# Dart_Controller_SCH.net
KiCad netlist of a schematic drawn in Altium Designer
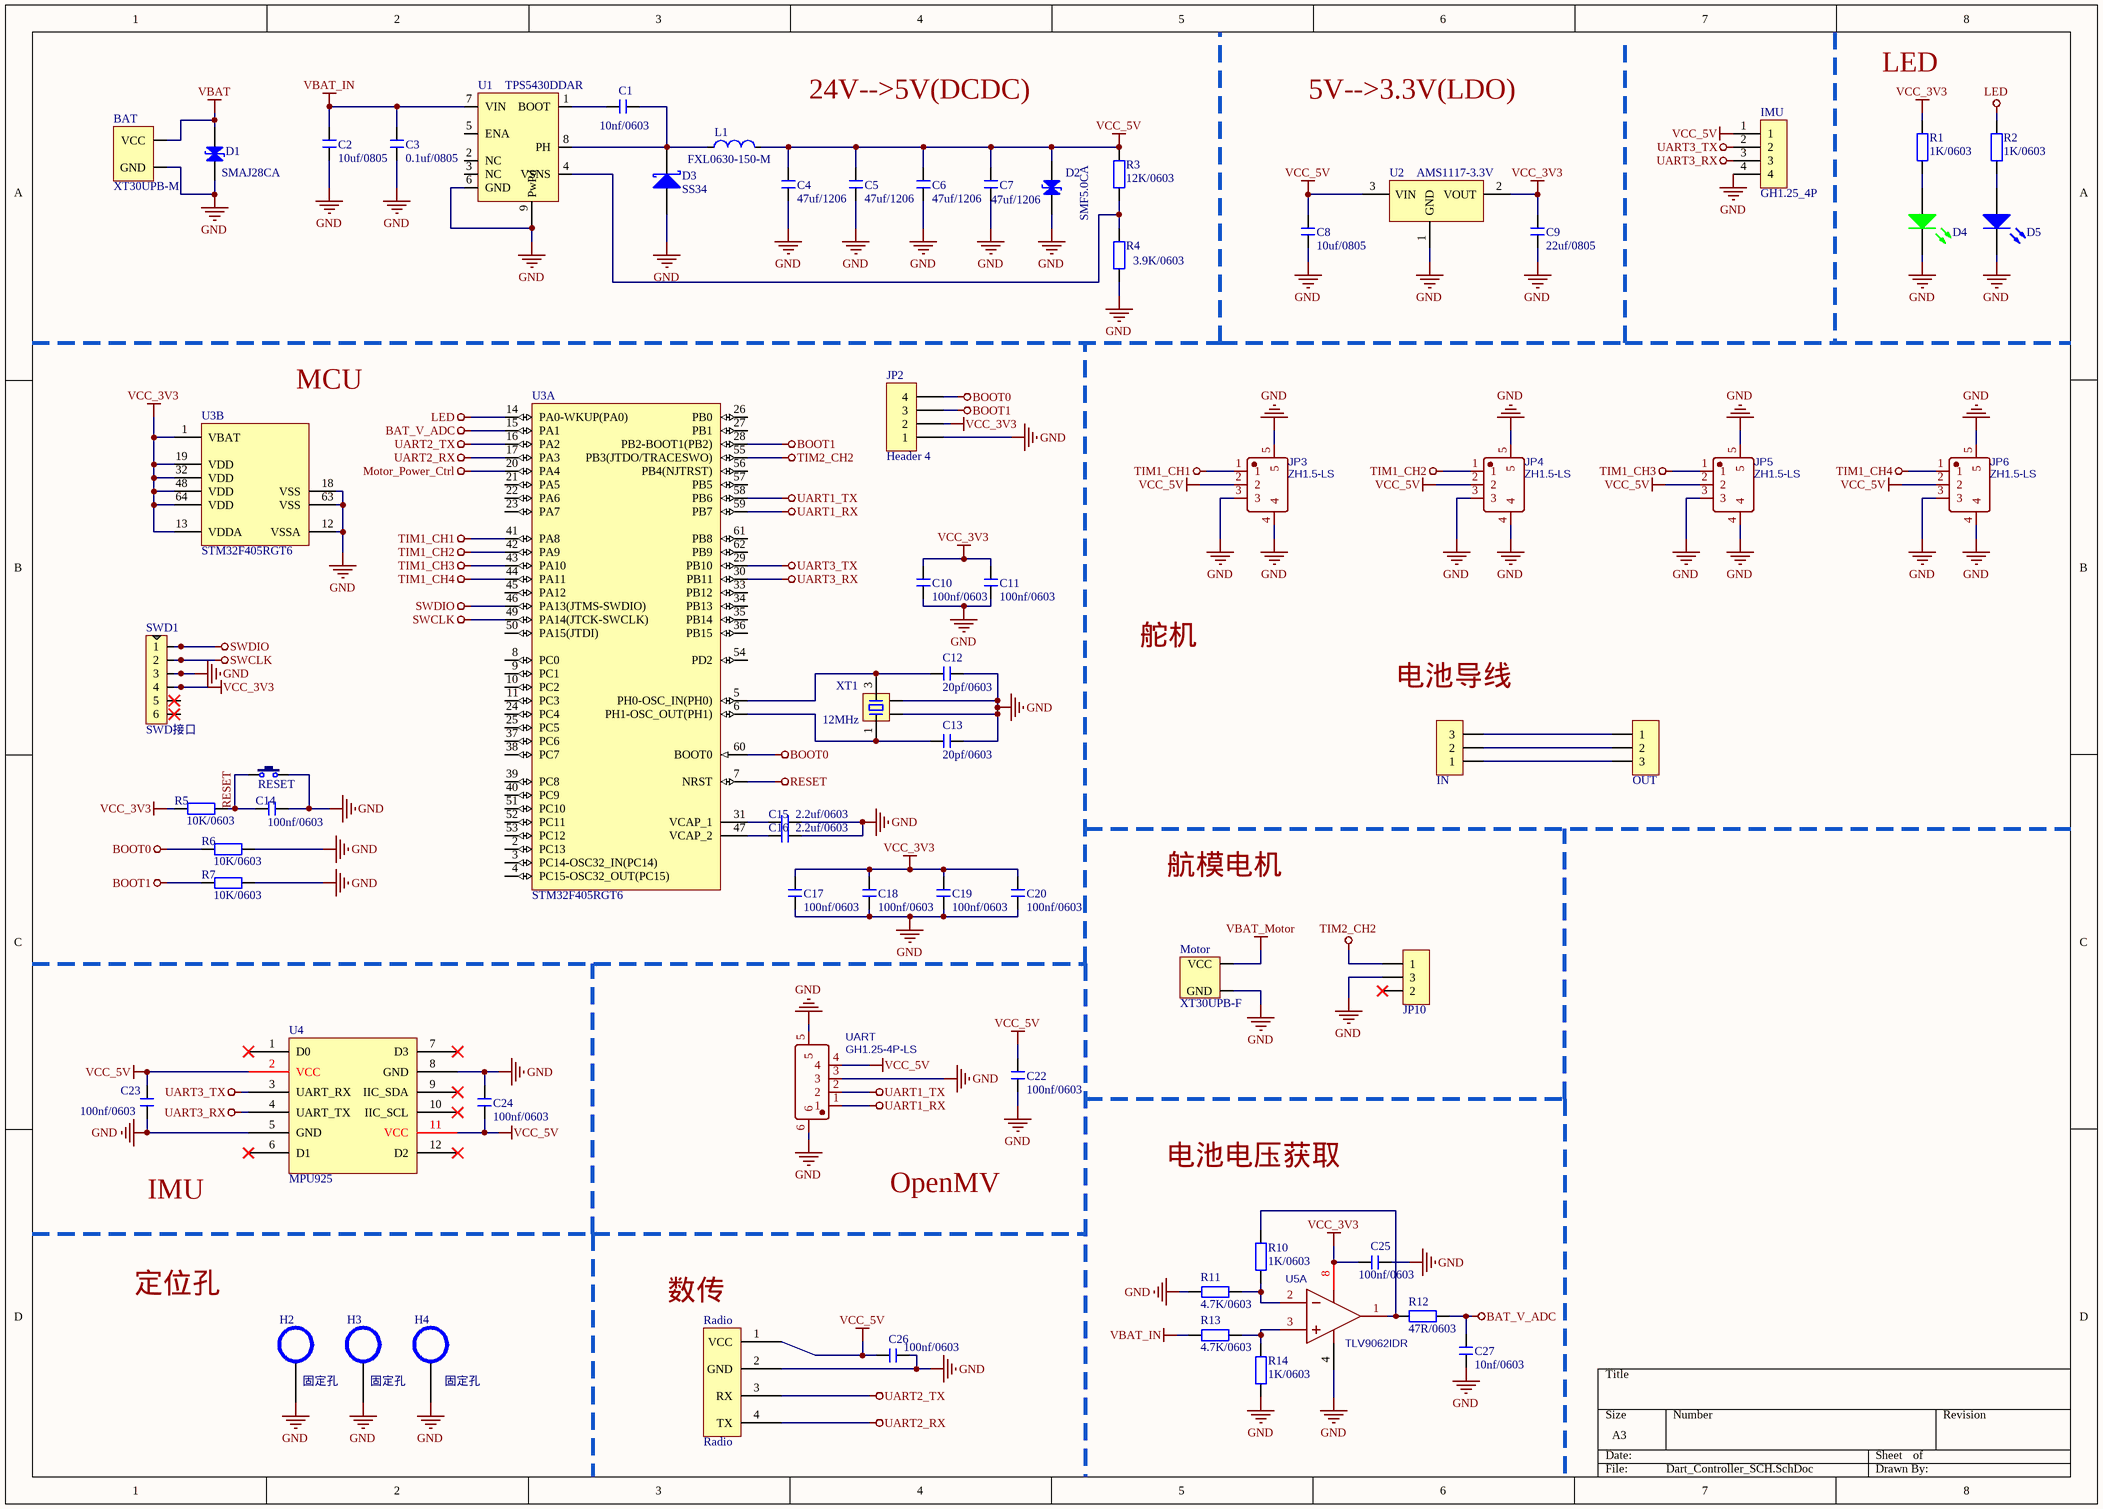
[diagram p0: Dart_Controller_SCH.SchDoc]

(export (version "E")
  (design (tool "Eeschema 10.0.6"))
  (components
    (comp (ref "BAT")
      (value "XT30UPB-M")
      (footprint "XT30PW-M")
      (description "公头(立式）")
      (libsource (lib "Dart_Controller_Schlib") (part "XT30-PW-M"))
    )
    (comp (ref "C1")
      (value "10nf/0603")
      (footprint "C 0603_M")
      (description "贴片电容")
      (libsource (lib "Dart_Controller_Schlib") (part "C 0603"))
    )
    (comp (ref "C2")
      (value "10uf/0805")
      (footprint "C 0805_M")
      (description "贴片电容")
      (libsource (lib "Dart_Controller_Schlib") (part "C 0805"))
    )
    (comp (ref "C3")
      (value "0.1uf/0805")
      (footprint "C 0805_M")
      (description "贴片电容")
      (libsource (lib "Dart_Controller_Schlib") (part "C 0805"))
    )
    (comp (ref "C4")
      (value "47uf/1206")
      (footprint "C 1206_M")
      (description "贴片电容")
      (libsource (lib "Dart_Controller_Schlib") (part "C 1206"))
    )
    (comp (ref "C5")
      (value "47uf/1206")
      (footprint "C 1206_M")
      (description "贴片电容")
      (libsource (lib "Dart_Controller_Schlib") (part "C 1206"))
    )
    (comp (ref "C6")
      (value "47uf/1206")
      (footprint "C 1206_M")
      (description "贴片电容")
      (libsource (lib "Dart_Controller_Schlib") (part "C 1206"))
    )
    (comp (ref "C7")
      (value "47uf/1206")
      (footprint "C 1206_M")
      (description "贴片电容")
      (libsource (lib "Dart_Controller_Schlib") (part "C 1206"))
    )
    (comp (ref "C8")
      (value "10uf/0805")
      (footprint "C 0805_M")
      (description "贴片电容")
      (libsource (lib "Dart_Controller_Schlib") (part "C 0805"))
    )
    (comp (ref "C9")
      (value "22uf/0805")
      (footprint "C 0805_M")
      (description "贴片电容")
      (libsource (lib "Dart_Controller_Schlib") (part "C 0805"))
    )
    (comp (ref "C10")
      (value "100nf/0603")
      (footprint "C 0603_M")
      (description "贴片电容")
      (libsource (lib "Dart_Controller_Schlib") (part "C 0603"))
    )
    (comp (ref "C11")
      (value "100nf/0603")
      (footprint "C 0603_M")
      (description "贴片电容")
      (libsource (lib "Dart_Controller_Schlib") (part "C 0603"))
    )
    (comp (ref "C12")
      (value "20pf/0603")
      (footprint "C 0603_M")
      (description "贴片电容")
      (libsource (lib "Dart_Controller_Schlib") (part "C 0603"))
    )
    (comp (ref "C13")
      (value "20pf/0603")
      (footprint "C 0603_M")
      (description "贴片电容")
      (libsource (lib "Dart_Controller_Schlib") (part "C 0603"))
    )
    (comp (ref "C14")
      (value "100nf/0603")
      (footprint "C 0603_M")
      (description "贴片电容")
      (libsource (lib "Dart_Controller_Schlib") (part "C 0603"))
    )
    (comp (ref "C15")
      (value "2.2uf/0603")
      (footprint "C 0603_M")
      (description "贴片电容")
      (libsource (lib "Dart_Controller_Schlib") (part "C 0603"))
    )
    (comp (ref "C16")
      (value "2.2uf/0603")
      (footprint "C 0603_M")
      (description "贴片电容")
      (libsource (lib "Dart_Controller_Schlib") (part "C 0603"))
    )
    (comp (ref "C17")
      (value "100nf/0603")
      (footprint "C 0603_M")
      (description "贴片电容")
      (libsource (lib "Dart_Controller_Schlib") (part "C 0603"))
    )
    (comp (ref "C18")
      (value "100nf/0603")
      (footprint "C 0603_M")
      (description "贴片电容")
      (libsource (lib "Dart_Controller_Schlib") (part "C 0603"))
    )
    (comp (ref "C19")
      (value "100nf/0603")
      (footprint "C 0603_M")
      (description "贴片电容")
      (libsource (lib "Dart_Controller_Schlib") (part "C 0603"))
    )
    (comp (ref "C20")
      (value "100nf/0603")
      (footprint "C 0603_M")
      (description "贴片电容")
      (libsource (lib "Dart_Controller_Schlib") (part "C 0603"))
    )
    (comp (ref "C22")
      (value "100nf/0603")
      (footprint "C 0603_M")
      (description "贴片电容")
      (libsource (lib "Dart_Controller_Schlib") (part "C 0603"))
    )
    (comp (ref "C23")
      (value "100nf/0603")
      (footprint "C 0603_M")
      (description "贴片电容")
      (libsource (lib "Dart_Controller_Schlib") (part "C 0603"))
    )
    (comp (ref "C24")
      (value "100nf/0603")
      (footprint "C 0603_M")
      (description "贴片电容")
      (libsource (lib "Dart_Controller_Schlib") (part "C 0603"))
    )
    (comp (ref "C25")
      (value "100nf/0603")
      (footprint "C 0603_M")
      (description "贴片电容")
      (libsource (lib "Cap_Mananger_Schlib") (part "C 0603"))
    )
    (comp (ref "C26")
      (value "100nf/0603")
      (footprint "C 0603_M")
      (description "贴片电容")
      (libsource (lib "Dart_Controller_Schlib") (part "C 0603"))
    )
    (comp (ref "C27")
      (value "10nf/0603")
      (footprint "C 0603_M")
      (description "贴片电容")
      (libsource (lib "Cap_Mananger_Schlib") (part "C 0603"))
    )
    (comp (ref "D1")
      (value "SMAJ28CA")
      (footprint "SMA")
      (description "双向瞬态电压抑制二极管")
      (libsource (lib "Dart_Controller_Schlib") (part "SMAJ28CA"))
    )
    (comp (ref "D2")
      (value "SMF5.0CA")
      (footprint "SOD-123FL_L2.8-W1.8-LS3.7-BI")
      (description "双向瞬态电压抑制二极管")
      (libsource (lib "Dart_Controller_Schlib") (part "SMF5.0CA"))
    )
    (comp (ref "D3")
      (value "SS34")
      (footprint "SMA")
      (description "肖特基二极管")
      (libsource (lib "Dart_Controller_Schlib") (part "SS34"))
    )
    (comp (ref "D4")
      (value "LED_G/0603")
      (footprint "LED-0603G")
      (description "发光二极管")
      (fields (field (name "PUBLISHER") "Altium Limited"))
      (libsource (lib "Dart_Controller_Schlib") (part "LED_G_1"))
    )
    (comp (ref "D5")
      (value "LED_B/0603")
      (footprint "LED-0603B")
      (description "发光二极管")
      (fields (field (name "PUBLISHER") "Altium Limited"))
      (libsource (lib "Dart_Controller_Schlib") (part "LED_B_1"))
    )
    (comp (ref "H2") (value "固定孔") (footprint "铜柱孔") (libsource (lib "Dart_Controller_Schlib") (part "铜柱孔")))
    (comp (ref "H3") (value "固定孔") (footprint "铜柱孔") (libsource (lib "Dart_Controller_Schlib") (part "铜柱孔")))
    (comp (ref "H4") (value "固定孔") (footprint "铜柱孔") (libsource (lib "Dart_Controller_Schlib") (part "铜柱孔")))
    (comp (ref "IMU")
      (value "GH1.25_4P")
      (footprint "GH1.25-WS-4P")
      (description "GH1,25_4P")
      (libsource (lib "Dart_Controller_Schlib") (part "GH1.25_4P"))
    )
    (comp (ref "IN")
      (value "HDR-1X3")
      (footprint "XH2.54-LI-3P")
      (description "3P接插件")
      (fields (field (name "版权归属") "封装库来自淘宝 ID：黄晶宝石"))
      (libsource (lib "Dart_Controller_Schlib") (part "Header 3_1"))
    )
    (comp (ref "JP2")
      (value "Header 4")
      (footprint "HDR2.54-LI-4P")
      (description "Header, 4-Pin")
      (fields (field (name "PUBLISHER") "Altium Limited"))
      (libsource (lib "Dart_Controller_Schlib") (part "Header 4"))
    )
    (comp (ref "JP3")
      (value "ZH1.5-LS")
      (footprint "ZH1.5")
      (fields
        (field (name "MANUFACTURER") "HCTL(华灿天禄)")
        (field (name "MANUFACTURER PART") "HC-ZH-3PLT")
        (field (name "CONTRIBUTOR") "LCSC")
      )
      (libsource (lib "Dart_Controller_Schlib") (part "ZH1.5-LS"))
    )
    (comp (ref "JP4")
      (value "ZH1.5-LS")
      (footprint "ZH1.5")
      (fields
        (field (name "MANUFACTURER") "HCTL(华灿天禄)")
        (field (name "MANUFACTURER PART") "HC-ZH-3PLT")
        (field (name "CONTRIBUTOR") "LCSC")
      )
      (libsource (lib "Dart_Controller_Schlib") (part "ZH1.5-LS"))
    )
    (comp (ref "JP5")
      (value "ZH1.5-LS")
      (footprint "ZH1.5")
      (fields
        (field (name "MANUFACTURER") "HCTL(华灿天禄)")
        (field (name "MANUFACTURER PART") "HC-ZH-3PLT")
        (field (name "CONTRIBUTOR") "LCSC")
      )
      (libsource (lib "Dart_Controller_Schlib") (part "ZH1.5-LS"))
    )
    (comp (ref "JP6")
      (value "ZH1.5-LS")
      (footprint "ZH1.5")
      (fields
        (field (name "MANUFACTURER") "HCTL(华灿天禄)")
        (field (name "MANUFACTURER PART") "HC-ZH-3PLT")
        (field (name "CONTRIBUTOR") "LCSC")
      )
      (libsource (lib "Dart_Controller_Schlib") (part "ZH1.5-LS"))
    )
    (comp (ref "JP10")
      (value "Header 2")
      (footprint "HDR2.54-WI-3P")
      (description "3P接插件")
      (fields (field (name "版权归属") "封装库来自淘宝 ID：黄晶宝石"))
      (libsource (lib "Dart_Controller_Schlib") (part "Header 3_3"))
    )
    (comp (ref "L1")
      (value "FXL0630-150-M")
      (footprint "L-SMD-0630")
      (description "功率电感")
      (libsource (lib "Dart_Controller_Schlib") (part "FXL0630-150-M"))
    )
    (comp (ref "Motor")
      (value "XT30UPB-F")
      (footprint "XT30PW-F")
      (description "母头（卧式）")
      (libsource (lib "Dart_Controller_Schlib") (part "XT30-PW-F"))
    )
    (comp (ref "OUT")
      (value "HDR-1X3")
      (footprint "XH2.54-WI-3P")
      (description "3P接插件")
      (fields (field (name "版权归属") "封装库来自淘宝 ID：黄晶宝石"))
      (libsource (lib "Dart_Controller_Schlib") (part "Header 3"))
    )
    (comp (ref "R1")
      (value "1K/0603")
      (footprint "R 0603_M")
      (description "贴片电阻")
      (fields (field (name "版权归属") "来自淘宝 ID：黄晶宝石"))
      (libsource (lib "Dart_Controller_Schlib") (part "R 0603"))
    )
    (comp (ref "R2")
      (value "1K/0603")
      (footprint "R 0603_M")
      (description "贴片电阻")
      (fields (field (name "版权归属") "来自淘宝 ID：黄晶宝石"))
      (libsource (lib "Dart_Controller_Schlib") (part "R 0603"))
    )
    (comp (ref "R3")
      (value "12K/0603")
      (footprint "R 0603_M")
      (description "贴片电阻")
      (fields (field (name "版权归属") "来自淘宝 ID：黄晶宝石"))
      (libsource (lib "Dart_Controller_Schlib") (part "R 0603"))
    )
    (comp (ref "R4")
      (value "3.9K/0603")
      (footprint "R 0603_M")
      (description "贴片电阻")
      (fields (field (name "版权归属") "来自淘宝 ID：黄晶宝石"))
      (libsource (lib "Dart_Controller_Schlib") (part "R 0603"))
    )
    (comp (ref "R5")
      (value "10K/0603")
      (footprint "R 0603_M")
      (description "贴片电阻")
      (fields (field (name "版权归属") "来自淘宝 ID：黄晶宝石"))
      (libsource (lib "Dart_Controller_Schlib") (part "R 0603"))
    )
    (comp (ref "R6")
      (value "10K/0603")
      (footprint "R 0603_M")
      (description "贴片电阻")
      (fields (field (name "版权归属") "来自淘宝 ID：黄晶宝石"))
      (libsource (lib "Dart_Controller_Schlib") (part "R 0603"))
    )
    (comp (ref "R7")
      (value "10K/0603")
      (footprint "R 0603_M")
      (description "贴片电阻")
      (fields (field (name "版权归属") "来自淘宝 ID：黄晶宝石"))
      (libsource (lib "Dart_Controller_Schlib") (part "R 0603"))
    )
    (comp (ref "R10")
      (value "1K/0603")
      (footprint "R 0603_M")
      (description "贴片电阻")
      (fields (field (name "版权归属") "来自淘宝 ID：黄晶宝石"))
      (libsource (lib "Cap_Mananger_Schlib") (part "R 0603"))
    )
    (comp (ref "R11")
      (value "4.7K/0603")
      (footprint "R 0603_M")
      (description "贴片电阻")
      (fields (field (name "版权归属") "来自淘宝 ID：黄晶宝石"))
      (libsource (lib "Cap_Mananger_Schlib") (part "R 0603"))
    )
    (comp (ref "R12")
      (value "47R/0603")
      (footprint "R 0603_M")
      (description "贴片电阻")
      (fields (field (name "版权归属") "来自淘宝 ID：黄晶宝石"))
      (libsource (lib "Cap_Mananger_Schlib") (part "R 0603"))
    )
    (comp (ref "R13")
      (value "4.7K/0603")
      (footprint "R 0603_M")
      (description "贴片电阻")
      (fields (field (name "版权归属") "来自淘宝 ID：黄晶宝石"))
      (libsource (lib "Cap_Mananger_Schlib") (part "R 0603"))
    )
    (comp (ref "R14")
      (value "1K/0603")
      (footprint "R 0603_M")
      (description "贴片电阻")
      (fields (field (name "版权归属") "来自淘宝 ID：黄晶宝石"))
      (libsource (lib "Cap_Mananger_Schlib") (part "R 0603"))
    )
    (comp (ref "Radio")
      (value "Radio")
      (footprint "Radio")
      (description "无线电-匿名数传")
      (libsource (lib "Dart_Controller_Schlib") (part "Radio"))
    )
    (comp (ref "RESET")
      (value "3x6x5")
      (footprint "TSW SMD-3*6*2.5")
      (description "3x6轻触开关")
      (fields (field (name "版权归属") "封装库来自淘宝 ID：黄晶宝石"))
      (libsource (lib "Dart_Controller_Schlib") (part "TSW 3x6"))
    )
    (comp (ref "SWD1")
      (value "SWD接口")
      (footprint "MX 1.25-WS-4P")
      (description "4P")
      (libsource (lib "Schlib_2.0") (part "SWD接口"))
    )
    (comp (ref "U1")
      (value "TPS5430DDAR")
      (footprint "ESOP8")
      (description "降压芯片")
      (libsource (lib "Dart_Controller_Schlib") (part "TPS5430DDAR"))
    )
    (comp (ref "U2")
      (value "AMS1117-3.3V")
      (footprint "SOT-89")
      (description "LDO")
      (libsource (lib "Dart_Controller_Schlib") (part "AMS1117-3.3V(SOT-89)"))
    )
    (comp (ref "U3")
      (value "STM32F405RGT6")
      (footprint "LQFP64 10x10_N")
      (fields (field (name "MANUFACTURER") "STMicroelectronics"))
      (libsource (lib "Dart_Controller_Schlib") (part "STM32F405RGT6"))
    )
    (comp (ref "U4")
      (value "MPU925")
      (footprint "JY901B_MPU9250")
      (libsource (lib "Dart_Controller_Schlib") (part "IMU"))
    )
    (comp (ref "U5")
      (value "TLV9062IDR")
      (footprint "SOP8_N")
      (description "运算放大器")
      (fields
        (field (name "MANUFACTURER") "TI(德州仪器)")
        (field (name "MANUFACTURER PART") "OPA365AIDBVR")
        (field (name "CONTRIBUTOR") "LCSC")
      )
      (libsource (lib "Scap_Schlib_v3.3") (part "TLV9062IDR"))
    )
    (comp (ref "UART")
      (value "GH1.25-4P-LS")
      (footprint "GH1.25-LS-4P")
      (fields
        (field (name "MANUFACTURER") "XUNPU(讯普)")
        (field (name "MANUFACTURER PART") "WAFER-GH1.25-4PLB")
        (field (name "CONTRIBUTOR") "lcsc")
      )
      (libsource (lib "Dart_Controller_Schlib") (part "GH1.25-4P-LS"))
    )
    (comp (ref "XT1")
      (value "12MHz")
      (footprint "XTAL_3225_4P")
      (description "无源晶振/外接20pf负载电容")
      (libsource (lib "Dart_Controller_Schlib") (part "X322512MSB4SI"))
    )
  )
  (nets
    (net (code "1") (name "BAT_V_ADC") (class "Default")
      (node (ref "C27") (pin "2") (pinfunction "2_2") (pintype "passive"))
      (node (ref "R12") (pin "2") (pinfunction "2_2") (pintype "passive"))
      (node (ref "U3") (pin "15") (pinfunction "PA1_15") (pintype "bidirectional"))
    )
    (net (code "2") (name "BOOT0") (class "Default")
      (node (ref "JP2") (pin "4") (pinfunction "4_4") (pintype "passive"))
      (node (ref "R6") (pin "2") (pinfunction "2_2") (pintype "passive"))
      (node (ref "U3") (pin "60") (pinfunction "BOOT0_60") (pintype "input"))
    )
    (net (code "3") (name "BOOT1") (class "Default")
      (node (ref "JP2") (pin "3") (pinfunction "3_3") (pintype "passive"))
      (node (ref "R7") (pin "2") (pinfunction "2_2") (pintype "passive"))
      (node (ref "U3") (pin "28") (pinfunction "PB2-BOOT1(PB2)_28") (pintype "bidirectional"))
    )
    (net (code "4") (name "GND") (class "Default")
      (node (ref "BAT") (pin "2") (pinfunction "GND_2") (pintype "passive"))
      (node (ref "C10") (pin "1") (pinfunction "1_1") (pintype "passive"))
      (node (ref "C11") (pin "1") (pinfunction "1_1") (pintype "passive"))
      (node (ref "C12") (pin "2") (pinfunction "2_2") (pintype "passive"))
      (node (ref "C13") (pin "2") (pinfunction "2_2") (pintype "passive"))
      (node (ref "C14") (pin "1") (pinfunction "1_1") (pintype "passive"))
      (node (ref "C15") (pin "2") (pinfunction "2_2") (pintype "passive"))
      (node (ref "C16") (pin "2") (pinfunction "2_2") (pintype "passive"))
      (node (ref "C17") (pin "1") (pinfunction "1_1") (pintype "passive"))
      (node (ref "C18") (pin "1") (pinfunction "1_1") (pintype "passive"))
      (node (ref "C19") (pin "1") (pinfunction "1_1") (pintype "passive"))
      (node (ref "C2") (pin "1") (pinfunction "1_1") (pintype "passive"))
      (node (ref "C20") (pin "1") (pinfunction "1_1") (pintype "passive"))
      (node (ref "C22") (pin "2") (pinfunction "2_2") (pintype "passive"))
      (node (ref "C23") (pin "1") (pinfunction "1_1") (pintype "passive"))
      (node (ref "C24") (pin "2") (pinfunction "2_2") (pintype "passive"))
      (node (ref "C25") (pin "1") (pinfunction "1_1") (pintype "passive"))
      (node (ref "C26") (pin "2") (pinfunction "2_2") (pintype "passive"))
      (node (ref "C27") (pin "1") (pinfunction "1_1") (pintype "passive"))
      (node (ref "C3") (pin "1") (pinfunction "1_1") (pintype "passive"))
      (node (ref "C4") (pin "1") (pinfunction "1_1") (pintype "passive"))
      (node (ref "C5") (pin "1") (pinfunction "1_1") (pintype "passive"))
      (node (ref "C6") (pin "1") (pinfunction "1_1") (pintype "passive"))
      (node (ref "C7") (pin "1") (pinfunction "1_1") (pintype "passive"))
      (node (ref "C8") (pin "1") (pinfunction "1_1") (pintype "passive"))
      (node (ref "C9") (pin "1") (pinfunction "1_1") (pintype "passive"))
      (node (ref "D1") (pin "2") (pinfunction "2_2") (pintype "passive"))
      (node (ref "D2") (pin "2") (pinfunction "2_2") (pintype "passive"))
      (node (ref "D3") (pin "1") (pinfunction "A_1") (pintype "passive"))
      (node (ref "D4") (pin "K") (pinfunction "K_K") (pintype "passive"))
      (node (ref "D5") (pin "K") (pinfunction "K_K") (pintype "passive"))
      (node (ref "H2") (pin "1") (pinfunction "11_1") (pintype "passive"))
      (node (ref "H3") (pin "1") (pinfunction "11_1") (pintype "passive"))
      (node (ref "H4") (pin "1") (pinfunction "11_1") (pintype "passive"))
      (node (ref "IMU") (pin "4") (pinfunction "4_4") (pintype "passive"))
      (node (ref "JP10") (pin "3") (pinfunction "3_3") (pintype "passive"))
      (node (ref "JP2") (pin "1") (pinfunction "1_1") (pintype "passive"))
      (node (ref "JP3") (pin "3") (pinfunction "3_3") (pintype "passive"))
      (node (ref "JP3") (pin "4") (pinfunction "4_4") (pintype "passive"))
      (node (ref "JP3") (pin "5") (pinfunction "5_5") (pintype "passive"))
      (node (ref "JP4") (pin "3") (pinfunction "3_3") (pintype "passive"))
      (node (ref "JP4") (pin "4") (pinfunction "4_4") (pintype "passive"))
      (node (ref "JP4") (pin "5") (pinfunction "5_5") (pintype "passive"))
      (node (ref "JP5") (pin "3") (pinfunction "3_3") (pintype "passive"))
      (node (ref "JP5") (pin "4") (pinfunction "4_4") (pintype "passive"))
      (node (ref "JP5") (pin "5") (pinfunction "5_5") (pintype "passive"))
      (node (ref "JP6") (pin "3") (pinfunction "3_3") (pintype "passive"))
      (node (ref "JP6") (pin "4") (pinfunction "4_4") (pintype "passive"))
      (node (ref "JP6") (pin "5") (pinfunction "5_5") (pintype "passive"))
      (node (ref "Motor") (pin "2") (pinfunction "GND_2") (pintype "passive"))
      (node (ref "R11") (pin "1") (pinfunction "1_1") (pintype "passive"))
      (node (ref "R14") (pin "1") (pinfunction "1_1") (pintype "passive"))
      (node (ref "R4") (pin "1") (pinfunction "1_1") (pintype "passive"))
      (node (ref "R6") (pin "1") (pinfunction "1_1") (pintype "passive"))
      (node (ref "R7") (pin "1") (pinfunction "1_1") (pintype "passive"))
      (node (ref "RESET") (pin "2") (pinfunction "2_2") (pintype "passive"))
      (node (ref "Radio") (pin "2") (pinfunction "GND_2") (pintype "passive"))
      (node (ref "SWD1") (pin "3") (pinfunction "3_3") (pintype "passive"))
      (node (ref "U1") (pin "6") (pinfunction "GND_6") (pintype "passive"))
      (node (ref "U1") (pin "9") (pinfunction "PwPd_9") (pintype "passive"))
      (node (ref "U2") (pin "1") (pinfunction "GND_1") (pintype "passive"))
      (node (ref "U3") (pin "12") (pinfunction "VSSA_12") (pintype "power_in"))
      (node (ref "U3") (pin "18") (pinfunction "VSS_18") (pintype "power_in"))
      (node (ref "U3") (pin "63") (pinfunction "VSS_63") (pintype "power_in"))
      (node (ref "U4") (pin "5") (pinfunction "GND_5") (pintype "passive"))
      (node (ref "U4") (pin "8") (pinfunction "GND_8") (pintype "passive"))
      (node (ref "U5") (pin "4") (pinfunction "VS-_4") (pintype "passive"))
      (node (ref "UART") (pin "3") (pinfunction "3_3") (pintype "passive"))
      (node (ref "UART") (pin "5") (pinfunction "5_5") (pintype "passive"))
      (node (ref "UART") (pin "6") (pinfunction "6_6") (pintype "passive"))
      (node (ref "XT1") (pin "2") (pinfunction "2_2") (pintype "passive"))
      (node (ref "XT1") (pin "4") (pinfunction "4_4") (pintype "passive"))
    )
    (net (code "5") (name "LED") (class "Default")
      (node (ref "R2") (pin "2") (pinfunction "2_2") (pintype "passive"))
      (node (ref "U3") (pin "14") (pinfunction "PA0-WKUP(PA0)_14") (pintype "bidirectional"))
    )
    (net (code "6") (name "Motor_Power_Ctrl") (class "Default")
      (node (ref "U3") (pin "20") (pinfunction "PA4_20") (pintype "bidirectional"))
    )
    (net (code "7") (name "Net-(D3-K)") (class "Default")
      (node (ref "C1") (pin "1") (pinfunction "1_1") (pintype "passive"))
      (node (ref "D3") (pin "2") (pinfunction "K_2") (pintype "passive"))
      (node (ref "L1") (pin "1") (pinfunction "1_1") (pintype "passive"))
      (node (ref "U1") (pin "8") (pinfunction "PH_8") (pintype "passive"))
    )
    (net (code "8") (name "Net-(D4-PadA)") (class "Default")
      (node (ref "D4") (pin "A") (pinfunction "A_A") (pintype "passive"))
      (node (ref "R1") (pin "1") (pinfunction "1_1") (pintype "passive"))
    )
    (net (code "9") (name "Net-(D5-PadA)") (class "Default")
      (node (ref "D5") (pin "A") (pinfunction "A_A") (pintype "passive"))
      (node (ref "R2") (pin "1") (pinfunction "1_1") (pintype "passive"))
    )
    (net (code "10") (name "Net-(IN-Pad1)") (class "Default")
      (node (ref "IN") (pin "1") (pinfunction "1_1") (pintype "passive"))
      (node (ref "OUT") (pin "3") (pinfunction "3_3") (pintype "passive"))
    )
    (net (code "11") (name "Net-(IN-Pad2)") (class "Default")
      (node (ref "IN") (pin "2") (pinfunction "2_2") (pintype "passive"))
      (node (ref "OUT") (pin "2") (pinfunction "2_2") (pintype "passive"))
    )
    (net (code "12") (name "Net-(IN-Pad3)") (class "Default")
      (node (ref "IN") (pin "3") (pinfunction "3_3") (pintype "passive"))
      (node (ref "OUT") (pin "1") (pinfunction "1_1") (pintype "passive"))
    )
    (net (code "13") (name "Net-(U1-BOOT)") (class "Default")
      (node (ref "C1") (pin "2") (pinfunction "2_2") (pintype "passive"))
      (node (ref "U1") (pin "1") (pinfunction "BOOT_1") (pintype "passive"))
    )
    (net (code "14") (name "Net-(U1-VSNS)") (class "Default")
      (node (ref "R3") (pin "1") (pinfunction "1_1") (pintype "passive"))
      (node (ref "R4") (pin "2") (pinfunction "2_2") (pintype "passive"))
      (node (ref "U1") (pin "4") (pinfunction "VSNS_4") (pintype "passive"))
    )
    (net (code "15") (name "Net-(U3A-PH0-OSC_IN(PH0))") (class "Default")
      (node (ref "C12") (pin "1") (pinfunction "1_1") (pintype "passive"))
      (node (ref "U3") (pin "5") (pinfunction "PH0-OSC_IN(PH0)_5") (pintype "bidirectional"))
      (node (ref "XT1") (pin "3") (pinfunction "3_3") (pintype "passive"))
    )
    (net (code "16") (name "Net-(U3A-PH1-OSC_OUT(PH1))") (class "Default")
      (node (ref "C13") (pin "1") (pinfunction "1_1") (pintype "passive"))
      (node (ref "U3") (pin "6") (pinfunction "PH1-OSC_OUT(PH1)_6") (pintype "bidirectional"))
      (node (ref "XT1") (pin "1") (pinfunction "1_1") (pintype "passive"))
    )
    (net (code "17") (name "Net-(U3A-VCAP_1)") (class "Default")
      (node (ref "C15") (pin "1") (pinfunction "1_1") (pintype "passive"))
      (node (ref "U3") (pin "31") (pinfunction "VCAP_1_31") (pintype "power_in"))
    )
    (net (code "18") (name "Net-(U3A-VCAP_2)") (class "Default")
      (node (ref "C16") (pin "1") (pinfunction "1_1") (pintype "passive"))
      (node (ref "U3") (pin "47") (pinfunction "VCAP_2_47") (pintype "power_in"))
    )
    (net (code "19") (name "Net-(U5A-IN+)") (class "Default")
      (node (ref "R13") (pin "2") (pinfunction "2_2") (pintype "passive"))
      (node (ref "R14") (pin "2") (pinfunction "2_2") (pintype "passive"))
      (node (ref "U5") (pin "3") (pinfunction "IN+_3") (pintype "passive"))
    )
    (net (code "20") (name "Net-(U5A-IN-)") (class "Default")
      (node (ref "R10") (pin "1") (pinfunction "1_1") (pintype "passive"))
      (node (ref "R11") (pin "2") (pinfunction "2_2") (pintype "passive"))
      (node (ref "U5") (pin "2") (pinfunction "IN-_2") (pintype "passive"))
    )
    (net (code "21") (name "Net-(U5A-OUT)") (class "Default")
      (node (ref "R10") (pin "2") (pinfunction "2_2") (pintype "passive"))
      (node (ref "R12") (pin "1") (pinfunction "1_1") (pintype "passive"))
      (node (ref "U5") (pin "1") (pinfunction "OUT_1") (pintype "passive"))
    )
    (net (code "22") (name "RESET") (class "Default")
      (node (ref "C14") (pin "2") (pinfunction "2_2") (pintype "passive"))
      (node (ref "R5") (pin "1") (pinfunction "1_1") (pintype "passive"))
      (node (ref "RESET") (pin "1") (pinfunction "1_1") (pintype "passive"))
      (node (ref "U3") (pin "7") (pinfunction "NRST_7") (pintype "bidirectional"))
    )
    (net (code "23") (name "SWCLK") (class "Default")
      (node (ref "SWD1") (pin "2") (pinfunction "2_2") (pintype "passive"))
      (node (ref "U3") (pin "49") (pinfunction "PA14(JTCK-SWCLK)_49") (pintype "bidirectional"))
    )
    (net (code "24") (name "SWDIO") (class "Default")
      (node (ref "SWD1") (pin "1") (pinfunction "1_1") (pintype "passive"))
      (node (ref "U3") (pin "46") (pinfunction "PA13(JTMS-SWDIO)_46") (pintype "bidirectional"))
    )
    (net (code "25") (name "TIM1_CH1") (class "Default")
      (node (ref "JP3") (pin "1") (pinfunction "1_1") (pintype "passive"))
      (node (ref "U3") (pin "41") (pinfunction "PA8_41") (pintype "bidirectional"))
    )
    (net (code "26") (name "TIM1_CH2") (class "Default")
      (node (ref "JP4") (pin "1") (pinfunction "1_1") (pintype "passive"))
      (node (ref "U3") (pin "42") (pinfunction "PA9_42") (pintype "bidirectional"))
    )
    (net (code "27") (name "TIM1_CH3") (class "Default")
      (node (ref "JP5") (pin "1") (pinfunction "1_1") (pintype "passive"))
      (node (ref "U3") (pin "43") (pinfunction "PA10_43") (pintype "bidirectional"))
    )
    (net (code "28") (name "TIM1_CH4") (class "Default")
      (node (ref "JP6") (pin "1") (pinfunction "1_1") (pintype "passive"))
      (node (ref "U3") (pin "44") (pinfunction "PA11_44") (pintype "bidirectional"))
    )
    (net (code "29") (name "TIM2_CH2") (class "Default")
      (node (ref "JP10") (pin "1") (pinfunction "1_1") (pintype "passive"))
      (node (ref "U3") (pin "55") (pinfunction "PB3(JTDO/TRACESWO)_55") (pintype "bidirectional"))
    )
    (net (code "30") (name "UART1_RX") (class "Default")
      (node (ref "U3") (pin "59") (pinfunction "PB7_59") (pintype "bidirectional"))
      (node (ref "UART") (pin "1") (pinfunction "1_1") (pintype "passive"))
    )
    (net (code "31") (name "UART1_TX") (class "Default")
      (node (ref "U3") (pin "58") (pinfunction "PB6_58") (pintype "bidirectional"))
      (node (ref "UART") (pin "2") (pinfunction "2_2") (pintype "passive"))
    )
    (net (code "32") (name "UART2_RX") (class "Default")
      (node (ref "Radio") (pin "4") (pinfunction "TX_4") (pintype "passive"))
      (node (ref "U3") (pin "17") (pinfunction "PA3_17") (pintype "bidirectional"))
    )
    (net (code "33") (name "UART2_TX") (class "Default")
      (node (ref "Radio") (pin "3") (pinfunction "RX_3") (pintype "passive"))
      (node (ref "U3") (pin "16") (pinfunction "PA2_16") (pintype "bidirectional"))
    )
    (net (code "34") (name "UART3_RX") (class "Default")
      (node (ref "IMU") (pin "3") (pinfunction "3_3") (pintype "passive"))
      (node (ref "U3") (pin "30") (pinfunction "PB11_30") (pintype "bidirectional"))
      (node (ref "U4") (pin "4") (pinfunction "UART_TX_4") (pintype "passive"))
    )
    (net (code "35") (name "UART3_TX") (class "Default")
      (node (ref "IMU") (pin "2") (pinfunction "2_2") (pintype "passive"))
      (node (ref "U3") (pin "29") (pinfunction "PB10_29") (pintype "bidirectional"))
      (node (ref "U4") (pin "3") (pinfunction "UART_RX_3") (pintype "passive"))
    )
    (net (code "36") (name "VBAT") (class "Default")
      (node (ref "BAT") (pin "1") (pinfunction "VCC_1") (pintype "passive"))
      (node (ref "D1") (pin "1") (pinfunction "1_1") (pintype "passive"))
    )
    (net (code "37") (name "VBAT_IN") (class "Default")
      (node (ref "C2") (pin "2") (pinfunction "2_2") (pintype "passive"))
      (node (ref "C3") (pin "2") (pinfunction "2_2") (pintype "passive"))
      (node (ref "R13") (pin "1") (pinfunction "1_1") (pintype "passive"))
      (node (ref "U1") (pin "7") (pinfunction "VIN_7") (pintype "passive"))
    )
    (net (code "38") (name "VBAT_Motor") (class "Default")
      (node (ref "Motor") (pin "1") (pinfunction "VCC_1") (pintype "passive"))
    )
    (net (code "39") (name "VCC_3V3") (class "Default")
      (node (ref "C10") (pin "2") (pinfunction "2_2") (pintype "passive"))
      (node (ref "C11") (pin "2") (pinfunction "2_2") (pintype "passive"))
      (node (ref "C17") (pin "2") (pinfunction "2_2") (pintype "passive"))
      (node (ref "C18") (pin "2") (pinfunction "2_2") (pintype "passive"))
      (node (ref "C19") (pin "2") (pinfunction "2_2") (pintype "passive"))
      (node (ref "C20") (pin "2") (pinfunction "2_2") (pintype "passive"))
      (node (ref "C25") (pin "2") (pinfunction "2_2") (pintype "passive"))
      (node (ref "C9") (pin "2") (pinfunction "2_2") (pintype "passive"))
      (node (ref "JP2") (pin "2") (pinfunction "2_2") (pintype "passive"))
      (node (ref "R1") (pin "2") (pinfunction "2_2") (pintype "passive"))
      (node (ref "R5") (pin "2") (pinfunction "2_2") (pintype "passive"))
      (node (ref "SWD1") (pin "4") (pinfunction "4_4") (pintype "passive"))
      (node (ref "U2") (pin "2") (pinfunction "VOUT_2") (pintype "passive"))
      (node (ref "U3") (pin "1") (pinfunction "VBAT_1") (pintype "power_in"))
      (node (ref "U3") (pin "13") (pinfunction "VDDA_13") (pintype "power_in"))
      (node (ref "U3") (pin "19") (pinfunction "VDD_19") (pintype "power_in"))
      (node (ref "U3") (pin "32") (pinfunction "VDD_32") (pintype "power_in"))
      (node (ref "U3") (pin "48") (pinfunction "VDD_48") (pintype "power_in"))
      (node (ref "U3") (pin "64") (pinfunction "VDD_64") (pintype "power_in"))
      (node (ref "U5") (pin "8") (pinfunction "VS+_8") (pintype "passive"))
    )
    (net (code "40") (name "VCC_5V") (class "Default")
      (node (ref "C22") (pin "1") (pinfunction "1_1") (pintype "passive"))
      (node (ref "C23") (pin "2") (pinfunction "2_2") (pintype "passive"))
      (node (ref "C24") (pin "1") (pinfunction "1_1") (pintype "passive"))
      (node (ref "C26") (pin "1") (pinfunction "1_1") (pintype "passive"))
      (node (ref "C4") (pin "2") (pinfunction "2_2") (pintype "passive"))
      (node (ref "C5") (pin "2") (pinfunction "2_2") (pintype "passive"))
      (node (ref "C6") (pin "2") (pinfunction "2_2") (pintype "passive"))
      (node (ref "C7") (pin "2") (pinfunction "2_2") (pintype "passive"))
      (node (ref "C8") (pin "2") (pinfunction "2_2") (pintype "passive"))
      (node (ref "D2") (pin "1") (pinfunction "1_1") (pintype "passive"))
      (node (ref "IMU") (pin "1") (pinfunction "1_1") (pintype "passive"))
      (node (ref "JP3") (pin "2") (pinfunction "2_2") (pintype "passive"))
      (node (ref "JP4") (pin "2") (pinfunction "2_2") (pintype "passive"))
      (node (ref "JP5") (pin "2") (pinfunction "2_2") (pintype "passive"))
      (node (ref "JP6") (pin "2") (pinfunction "2_2") (pintype "passive"))
      (node (ref "L1") (pin "2") (pinfunction "2_2") (pintype "passive"))
      (node (ref "R3") (pin "2") (pinfunction "2_2") (pintype "passive"))
      (node (ref "Radio") (pin "1") (pinfunction "VCC_1") (pintype "passive"))
      (node (ref "U2") (pin "3") (pinfunction "VIN_3") (pintype "passive"))
      (node (ref "U4") (pin "11") (pinfunction "VCC_11") (pintype "passive"))
      (node (ref "U4") (pin "2") (pinfunction "VCC_2") (pintype "passive"))
      (node (ref "UART") (pin "4") (pinfunction "4_4") (pintype "passive"))
    )
    (net (code "41") (name "unconnected-(JP10-Pad2)") (class "Default")
      (node (ref "JP10") (pin "2") (pinfunction "2_2") (pintype "passive+no_connect"))
    )
    (net (code "42") (name "unconnected-(SWD1-Pad5)") (class "Default")
      (node (ref "SWD1") (pin "5") (pinfunction "5_5") (pintype "passive"))
    )
    (net (code "43") (name "unconnected-(SWD1-Pad6)") (class "Default")
      (node (ref "SWD1") (pin "6") (pinfunction "6_6") (pintype "passive"))
    )
    (net (code "44") (name "unconnected-(U1-ENA-Pad5)") (class "Default")
      (node (ref "U1") (pin "5") (pinfunction "ENA_5") (pintype "passive"))
    )
    (net (code "45") (name "unconnected-(U1-NC-Pad2)") (class "Default")
      (node (ref "U1") (pin "2") (pinfunction "NC_2") (pintype "passive"))
    )
    (net (code "46") (name "unconnected-(U1-NC-Pad3)") (class "Default")
      (node (ref "U1") (pin "3") (pinfunction "NC_3") (pintype "passive"))
    )
    (net (code "47") (name "unconnected-(U3A-PA5-Pad21)") (class "Default")
      (node (ref "U3") (pin "21") (pinfunction "PA5_21") (pintype "bidirectional"))
    )
    (net (code "48") (name "unconnected-(U3A-PA6-Pad22)") (class "Default")
      (node (ref "U3") (pin "22") (pinfunction "PA6_22") (pintype "bidirectional"))
    )
    (net (code "49") (name "unconnected-(U3A-PA7-Pad23)") (class "Default")
      (node (ref "U3") (pin "23") (pinfunction "PA7_23") (pintype "bidirectional"))
    )
    (net (code "50") (name "unconnected-(U3A-PA12-Pad45)") (class "Default")
      (node (ref "U3") (pin "45") (pinfunction "PA12_45") (pintype "bidirectional"))
    )
    (net (code "51") (name "unconnected-(U3A-PA15(JTDI)-Pad50)") (class "Default")
      (node (ref "U3") (pin "50") (pinfunction "PA15(JTDI)_50") (pintype "bidirectional"))
    )
    (net (code "52") (name "unconnected-(U3A-PB0-Pad26)") (class "Default")
      (node (ref "U3") (pin "26") (pinfunction "PB0_26") (pintype "bidirectional"))
    )
    (net (code "53") (name "unconnected-(U3A-PB1-Pad27)") (class "Default")
      (node (ref "U3") (pin "27") (pinfunction "PB1_27") (pintype "bidirectional"))
    )
    (net (code "54") (name "unconnected-(U3A-PB4(NJTRST)-Pad56)") (class "Default")
      (node (ref "U3") (pin "56") (pinfunction "PB4(NJTRST)_56") (pintype "bidirectional"))
    )
    (net (code "55") (name "unconnected-(U3A-PB5-Pad57)") (class "Default")
      (node (ref "U3") (pin "57") (pinfunction "PB5_57") (pintype "bidirectional"))
    )
    (net (code "56") (name "unconnected-(U3A-PB8-Pad61)") (class "Default")
      (node (ref "U3") (pin "61") (pinfunction "PB8_61") (pintype "bidirectional"))
    )
    (net (code "57") (name "unconnected-(U3A-PB9-Pad62)") (class "Default")
      (node (ref "U3") (pin "62") (pinfunction "PB9_62") (pintype "bidirectional"))
    )
    (net (code "58") (name "unconnected-(U3A-PB12-Pad33)") (class "Default")
      (node (ref "U3") (pin "33") (pinfunction "PB12_33") (pintype "bidirectional"))
    )
    (net (code "59") (name "unconnected-(U3A-PB13-Pad34)") (class "Default")
      (node (ref "U3") (pin "34") (pinfunction "PB13_34") (pintype "bidirectional"))
    )
    (net (code "60") (name "unconnected-(U3A-PB14-Pad35)") (class "Default")
      (node (ref "U3") (pin "35") (pinfunction "PB14_35") (pintype "bidirectional"))
    )
    (net (code "61") (name "unconnected-(U3A-PB15-Pad36)") (class "Default")
      (node (ref "U3") (pin "36") (pinfunction "PB15_36") (pintype "bidirectional"))
    )
    (net (code "62") (name "unconnected-(U3A-PC0-Pad8)") (class "Default")
      (node (ref "U3") (pin "8") (pinfunction "PC0_8") (pintype "bidirectional"))
    )
    (net (code "63") (name "unconnected-(U3A-PC1-Pad9)") (class "Default")
      (node (ref "U3") (pin "9") (pinfunction "PC1_9") (pintype "bidirectional"))
    )
    (net (code "64") (name "unconnected-(U3A-PC2-Pad10)") (class "Default")
      (node (ref "U3") (pin "10") (pinfunction "PC2_10") (pintype "bidirectional"))
    )
    (net (code "65") (name "unconnected-(U3A-PC3-Pad11)") (class "Default")
      (node (ref "U3") (pin "11") (pinfunction "PC3_11") (pintype "bidirectional"))
    )
    (net (code "66") (name "unconnected-(U3A-PC4-Pad24)") (class "Default")
      (node (ref "U3") (pin "24") (pinfunction "PC4_24") (pintype "bidirectional"))
    )
    (net (code "67") (name "unconnected-(U3A-PC5-Pad25)") (class "Default")
      (node (ref "U3") (pin "25") (pinfunction "PC5_25") (pintype "bidirectional"))
    )
    (net (code "68") (name "unconnected-(U3A-PC6-Pad37)") (class "Default")
      (node (ref "U3") (pin "37") (pinfunction "PC6_37") (pintype "bidirectional"))
    )
    (net (code "69") (name "unconnected-(U3A-PC7-Pad38)") (class "Default")
      (node (ref "U3") (pin "38") (pinfunction "PC7_38") (pintype "bidirectional"))
    )
    (net (code "70") (name "unconnected-(U3A-PC8-Pad39)") (class "Default")
      (node (ref "U3") (pin "39") (pinfunction "PC8_39") (pintype "bidirectional"))
    )
    (net (code "71") (name "unconnected-(U3A-PC9-Pad40)") (class "Default")
      (node (ref "U3") (pin "40") (pinfunction "PC9_40") (pintype "bidirectional"))
    )
    (net (code "72") (name "unconnected-(U3A-PC10-Pad51)") (class "Default")
      (node (ref "U3") (pin "51") (pinfunction "PC10_51") (pintype "bidirectional"))
    )
    (net (code "73") (name "unconnected-(U3A-PC11-Pad52)") (class "Default")
      (node (ref "U3") (pin "52") (pinfunction "PC11_52") (pintype "bidirectional"))
    )
    (net (code "74") (name "unconnected-(U3A-PC12-Pad53)") (class "Default")
      (node (ref "U3") (pin "53") (pinfunction "PC12_53") (pintype "bidirectional"))
    )
    (net (code "75") (name "unconnected-(U3A-PC13-Pad2)") (class "Default")
      (node (ref "U3") (pin "2") (pinfunction "PC13_2") (pintype "bidirectional"))
    )
    (net (code "76") (name "unconnected-(U3A-PC14-OSC32_IN(PC14)-Pad3)") (class "Default")
      (node (ref "U3") (pin "3") (pinfunction "PC14-OSC32_IN(PC14)_3") (pintype "bidirectional"))
    )
    (net (code "77") (name "unconnected-(U3A-PC15-OSC32_OUT(PC15)-Pad4)") (class "Default")
      (node (ref "U3") (pin "4") (pinfunction "PC15-OSC32_OUT(PC15)_4") (pintype "bidirectional"))
    )
    (net (code "78") (name "unconnected-(U3A-PD2-Pad54)") (class "Default")
      (node (ref "U3") (pin "54") (pinfunction "PD2_54") (pintype "bidirectional"))
    )
    (net (code "79") (name "unconnected-(U4-D0-Pad1)") (class "Default")
      (node (ref "U4") (pin "1") (pinfunction "D0_1") (pintype "passive+no_connect"))
    )
    (net (code "80") (name "unconnected-(U4-D1-Pad6)") (class "Default")
      (node (ref "U4") (pin "6") (pinfunction "D1_6") (pintype "passive+no_connect"))
    )
    (net (code "81") (name "unconnected-(U4-D2-Pad12)") (class "Default")
      (node (ref "U4") (pin "12") (pinfunction "D2_12") (pintype "passive+no_connect"))
    )
    (net (code "82") (name "unconnected-(U4-D3-Pad7)") (class "Default")
      (node (ref "U4") (pin "7") (pinfunction "D3_7") (pintype "passive+no_connect"))
    )
    (net (code "83") (name "unconnected-(U4-IIC_SCL-Pad10)") (class "Default")
      (node (ref "U4") (pin "10") (pinfunction "IIC_SCL_10") (pintype "passive+no_connect"))
    )
    (net (code "84") (name "unconnected-(U4-IIC_SDA-Pad9)") (class "Default")
      (node (ref "U4") (pin "9") (pinfunction "IIC_SDA_9") (pintype "passive+no_connect"))
    )
  )
)
